# N64Connector.net
KiCad netlist of a schematic drawn in Altium Designer
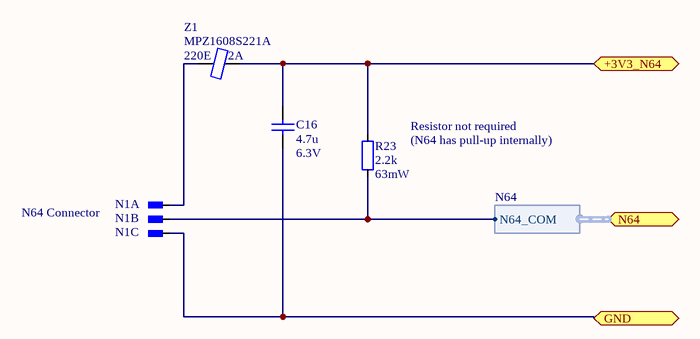
[diagram p0: N64Connector.SchDoc]

(export (version "E")
  (design (tool "Eeschema 10.0.6"))
  (components
    (comp (ref "C16")
      (value "4.7u")
      (footprint "SMD_CAP_0603")
      (fields (field (name "VALUE2") "6.3V") (field (name "Comment") "C_SMD_CER_4U7_6V3_10%_X5R_0603"))
      (libsource (lib "AM") (part "C_SMD_CER_4U7_6V3_10%_X5R_0603"))
    )
    (comp (ref "N1")
      (value "X_CONNECTOR_P2.54_D0.9_1X3")
      (footprint "THT_CON_P2.54_D0.9_1X3")
      (description "Pitch 2.54, Diameter 0.9mm, 1 row, 3 columns")
      (libsource (lib "AM") (part "X_CONNECTOR_P2.54_D0.9_1X3"))
    )
    (comp (ref "R23")
      (value "2.2k")
      (footprint "SMD_RES_0402")
      (description "2.2 kOhms ±0.5% 0.063W, 1/16W Chip Resistor 0402 (1005 Metric) Automotive AEC-Q200 Thin Film")
      (fields
        (field (name "VALUE2") "63mW")
        (field (name "Comment") "R_SMD_THINFILM_2K2_0W063_0%5_25PPM_0402")
      )
      (libsource (lib "AM") (part "R_SMD_THINFILM_2K2_0W063_0%5_25PPM_0402"))
    )
    (comp (ref "Z1")
      (value "220E")
      (footprint "SMD_RES_0603")
      (description "Ferrite Beads")
      (fields
        (field (name "TYPE") "MPZ1608S221A")
        (field (name "VALUE2") "2A")
        (field (name "Comment") "Z_SMD_FERRITE_2A_220E@100MHZ_0603")
      )
      (libsource (lib "AM") (part "Z_SMD_FERRITE_2A_220E@100MHZ_0603"))
    )
  )
  (nets
    (net (code "2") (name "/+3V3_N64") (class "Default")
      (node (ref "C16") (pin "2") (pinfunction "2_2") (pintype "passive"))
      (node (ref "R23") (pin "2") (pinfunction "2_2") (pintype "passive"))
      (node (ref "Z1") (pin "2") (pinfunction "2_2") (pintype "passive"))
    )
    (net (code "3") (name "/GND") (class "Default")
      (node (ref "C16") (pin "1") (pinfunction "1_1") (pintype "passive"))
      (node (ref "N1") (pin "3") (pinfunction "3_3") (pintype "passive"))
    )
    (net (code "5") (name "Net-(N1-Pad1)") (class "Default")
      (node (ref "N1") (pin "1") (pinfunction "1_1") (pintype "passive"))
      (node (ref "Z1") (pin "1") (pinfunction "1_1") (pintype "passive"))
    )
    (net (code "6") (name "Net-(N1-Pad2)") (class "Default")
      (node (ref "N1") (pin "2") (pinfunction "2_2") (pintype "passive"))
      (node (ref "R23") (pin "1") (pinfunction "1_1") (pintype "passive"))
    )
  )
)
